# Sheet1.net
KiCad netlist of a schematic drawn in Altium Designer
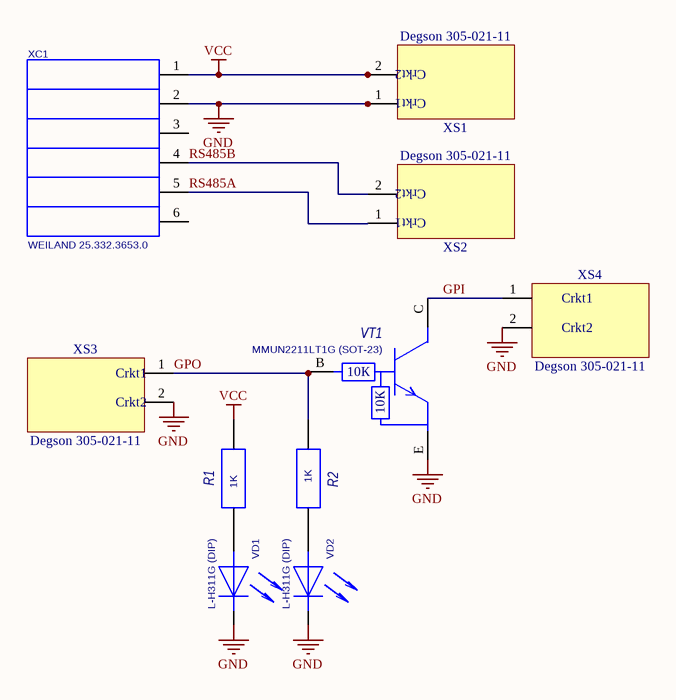
[diagram p0: Sheet1.SchDoc]

(export (version "E")
  (design (tool "Eeschema 10.0.6"))
  (components
    (comp (ref "R1")
      (value "1K")
      (footprint "RESC0603N")
      (description "R0603")
      (fields (field (name "MFG") "ф.Bourns"))
      (libsource (lib "pass_smd") (part "R0603"))
    )
    (comp (ref "R2")
      (value "1K")
      (footprint "RESC0603N")
      (description "R0603")
      (fields (field (name "MFG") "ф.Bourns"))
      (libsource (lib "pass_smd") (part "R0603"))
    )
    (comp (ref "VD1")
      (value "L-H311G (DIP)")
      (footprint "L-H311")
      (description "L-H311G")
      (libsource (lib "diodes") (part "L-H311G"))
    )
    (comp (ref "VD2")
      (value "L-H311G (DIP)")
      (footprint "L-H311")
      (description "L-H311G")
      (libsource (lib "diodes") (part "L-H311G"))
    )
    (comp (ref "VT1")
      (value "MMUN2211LT1G (SOT-23)")
      (footprint "SOT95P230-3N (SOT-23)")
      (description "MUN2211T1")
      (fields
        (field (name "CMPPARTNUM") "MMUN2211LT1G")
        (field (name "PARR1VALUE") "10К")
        (field (name "PARR2VALUE") "10К")
      )
      (libsource (lib "transistors") (part "MUN2211T1"))
    )
    (comp (ref "XC1")
      (value "WEILAND 25.332.3653.0")
      (footprint "WEILAND_25.332.3653.0")
      (description "WEILAND_6PIN_5MM")
      (libsource (lib "connectors") (part "WEILAND_6PIN_5MM"))
    )
    (comp (ref "XS1")
      (value "Degson 305-021-11")
      (footprint "305-021-11")
      (description "Клеммник винтовой, 2-контактный, 5мм, прямой")
      (fields (field (name "CMPPARTNUM") "305-021-11"))
      (libsource (lib "") (part "305-021-11_1"))
    )
    (comp (ref "XS2")
      (value "Degson 305-021-11")
      (footprint "305-021-11")
      (description "Клеммник винтовой, 2-контактный, 5мм, прямой")
      (fields (field (name "CMPPARTNUM") "305-021-11"))
      (libsource (lib "") (part "305-021-11_1"))
    )
    (comp (ref "XS3")
      (value "Degson 305-021-11")
      (footprint "305-021-11")
      (description "Клеммник винтовой, 2-контактный, 5мм, прямой")
      (fields (field (name "CMPPARTNUM") "305-021-11"))
      (libsource (lib "") (part "305-021-11_2"))
    )
    (comp (ref "XS4")
      (value "Degson 305-021-11")
      (footprint "305-021-11")
      (description "Клеммник винтовой, 2-контактный, 5мм, прямой")
      (fields (field (name "CMPPARTNUM") "305-021-11"))
      (libsource (lib "connectors") (part "305-021-11"))
    )
  )
  (nets
    (net (code "1") (name "/GPI") (class "Default")
      (node (ref "VT1") (pin "C") (pinfunction "C_C") (pintype "passive"))
      (node (ref "XS4") (pin "1") (pinfunction "1_1") (pintype "passive"))
    )
    (net (code "2") (name "/GPO") (class "Default")
      (node (ref "R2") (pin "1") (pinfunction "1_1") (pintype "passive"))
      (node (ref "VT1") (pin "B") (pinfunction "B_B") (pintype "passive"))
      (node (ref "XS3") (pin "1") (pinfunction "1_1") (pintype "passive"))
    )
    (net (code "3") (name "/RS485A") (class "Default")
      (node (ref "XC1") (pin "5") (pinfunction "5_5") (pintype "passive"))
      (node (ref "XS2") (pin "1") (pinfunction "1_1") (pintype "passive"))
    )
    (net (code "4") (name "/RS485B") (class "Default")
      (node (ref "XC1") (pin "4") (pinfunction "4_4") (pintype "passive"))
      (node (ref "XS2") (pin "2") (pinfunction "2_2") (pintype "passive"))
    )
    (net (code "5") (name "GND") (class "Default")
      (node (ref "VD1") (pin "2") (pinfunction "cathode_2") (pintype "passive"))
      (node (ref "VD2") (pin "2") (pinfunction "cathode_2") (pintype "passive"))
      (node (ref "VT1") (pin "E") (pinfunction "E_E") (pintype "passive"))
      (node (ref "XC1") (pin "2") (pinfunction "2_2") (pintype "passive"))
      (node (ref "XS1") (pin "1") (pinfunction "1_1") (pintype "passive"))
      (node (ref "XS3") (pin "2") (pinfunction "2_2") (pintype "passive"))
      (node (ref "XS4") (pin "2") (pinfunction "2_2") (pintype "passive"))
    )
    (net (code "6") (name "Net-(VD1-anod)") (class "Default")
      (node (ref "R1") (pin "1") (pinfunction "1_1") (pintype "passive"))
      (node (ref "VD1") (pin "1") (pinfunction "anod_1") (pintype "passive"))
    )
    (net (code "7") (name "Net-(VD2-anod)") (class "Default")
      (node (ref "R2") (pin "2") (pinfunction "2_2") (pintype "passive"))
      (node (ref "VD2") (pin "1") (pinfunction "anod_1") (pintype "passive"))
    )
    (net (code "8") (name "VCC") (class "Default")
      (node (ref "R1") (pin "2") (pinfunction "2_2") (pintype "passive"))
      (node (ref "XC1") (pin "1") (pinfunction "1_1") (pintype "passive"))
      (node (ref "XS1") (pin "2") (pinfunction "2_2") (pintype "passive"))
    )
    (net (code "9") (name "unconnected-(XC1-Pad3)") (class "Default")
      (node (ref "XC1") (pin "3") (pinfunction "3_3") (pintype "passive"))
    )
    (net (code "10") (name "unconnected-(XC1-Pad6)") (class "Default")
      (node (ref "XC1") (pin "6") (pinfunction "6_6") (pintype "passive"))
    )
  )
)
